# mimic4218_config.net
KiCad netlist of a schematic drawn in EAGLE
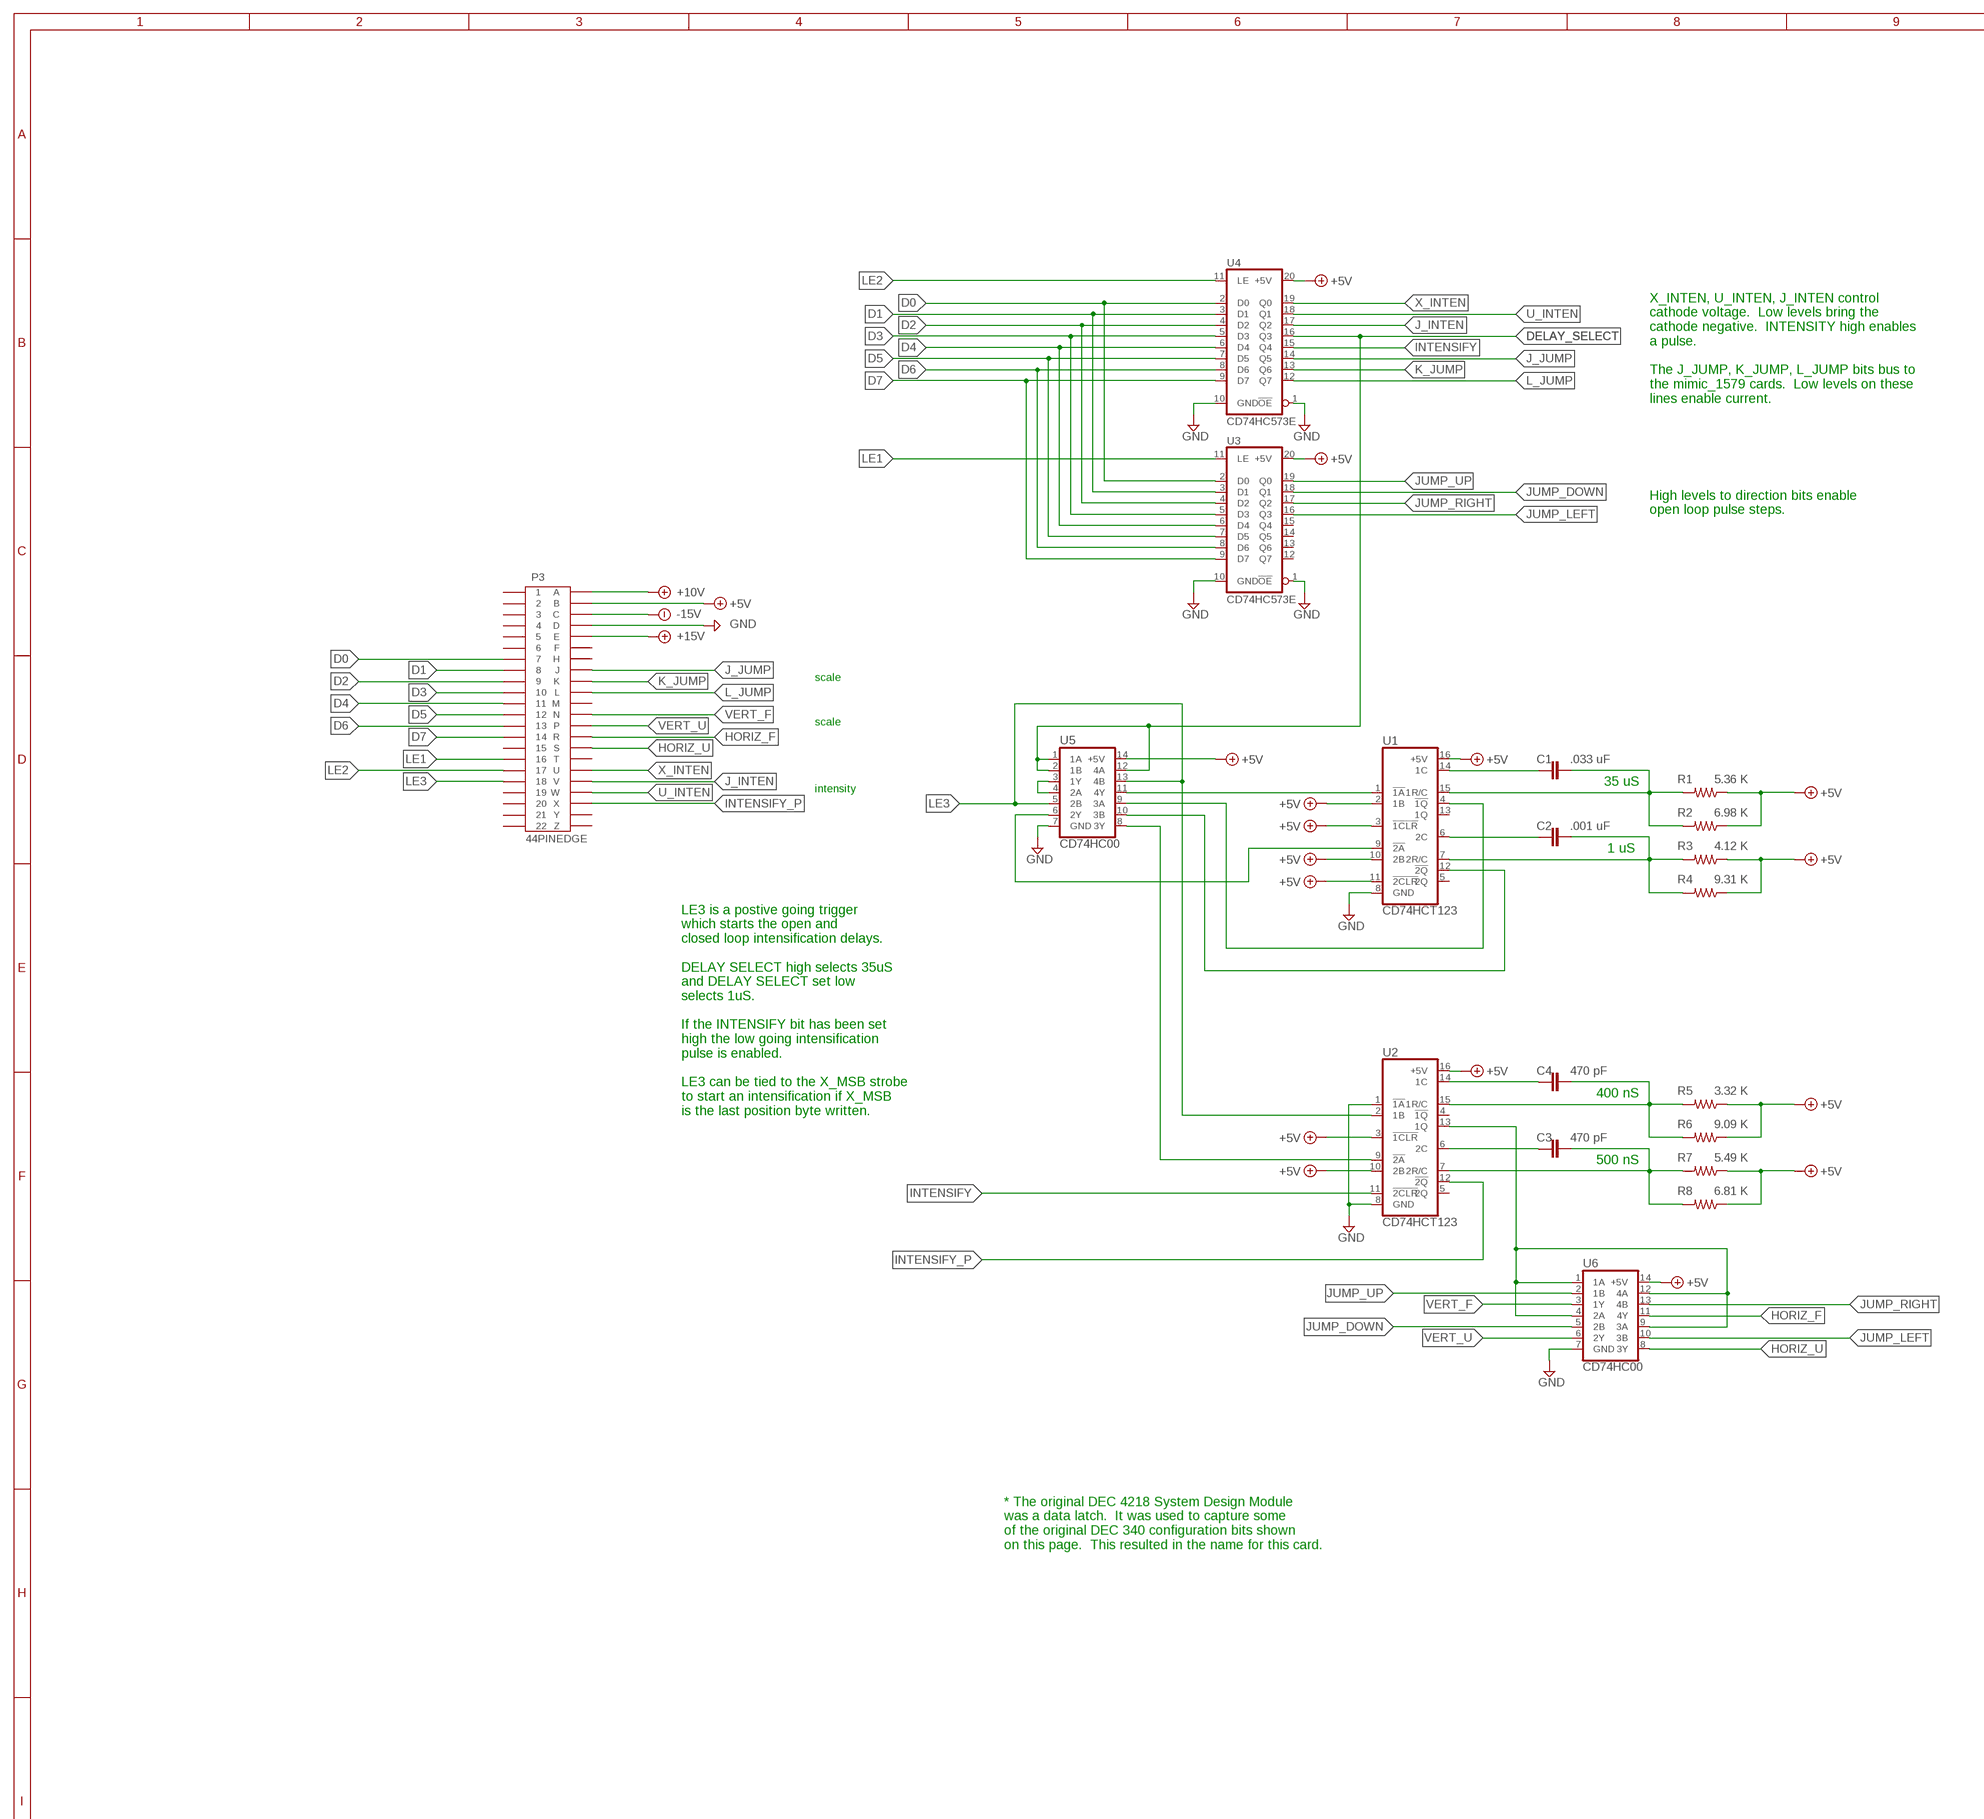
[diagram p0: schematic, sheet 1, part 1 of 2]
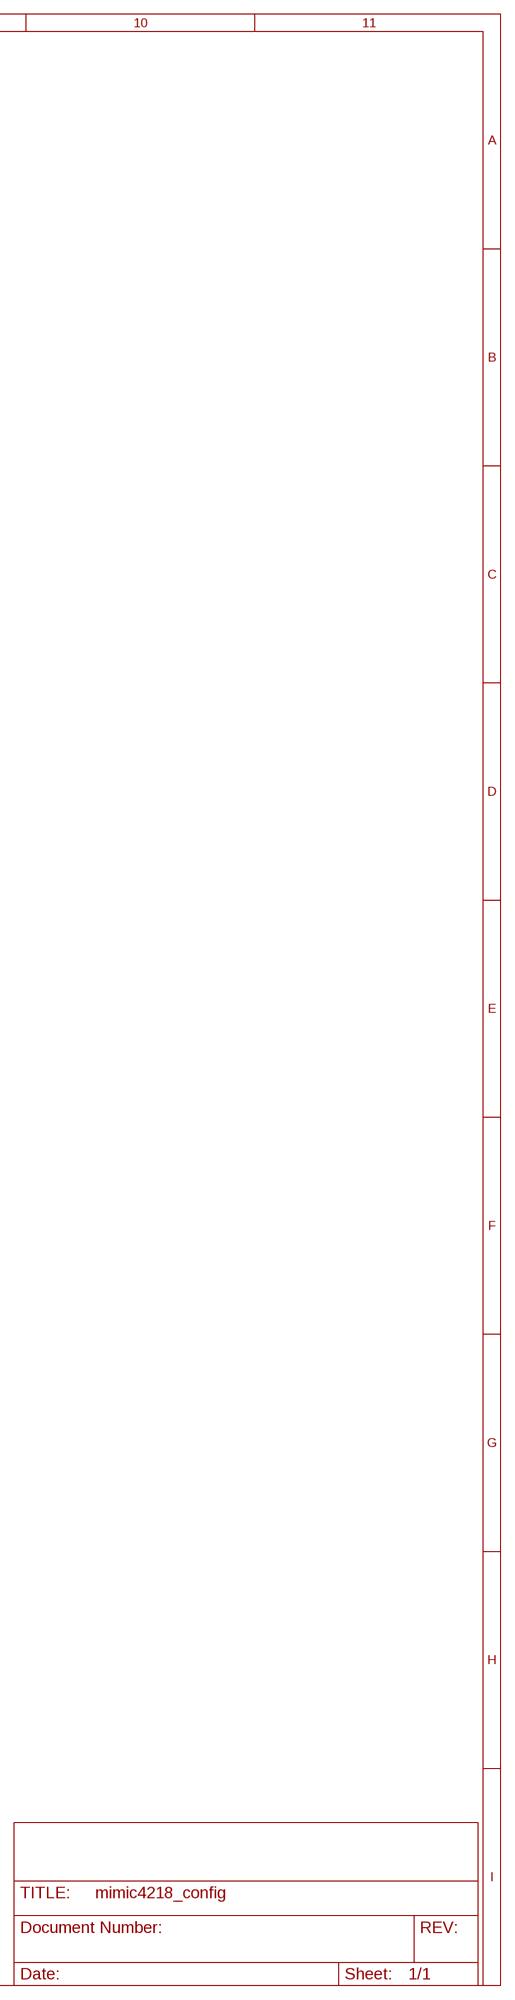
[diagram p1: schematic, sheet 1, part 2 of 2]

(export (version "E")
  (design (tool "Eeschema 10.0.6"))
  (components
    (comp (ref "C1")
      (value ".033 uF")
      (footprint "eagle-import:5MM_TH")
      (libsource (lib "eagle-import") (part "CAP_5MM"))
    )
    (comp (ref "C2")
      (value ".001 uF")
      (footprint "eagle-import:5MM_TH")
      (libsource (lib "eagle-import") (part "CAP_5MM"))
    )
    (comp (ref "C3")
      (value "470 pF")
      (footprint "eagle-import:5MM_TH")
      (libsource (lib "eagle-import") (part "CAP_5MM"))
    )
    (comp (ref "C4")
      (value "470 pF")
      (footprint "eagle-import:5MM_TH")
      (libsource (lib "eagle-import") (part "CAP_5MM"))
    )
    (comp (ref "P3")
      (value "44PINEDGE")
      (footprint "eagle-import:44PINEDGE")
      (libsource (lib "eagle-import") (part "44PINEDGE"))
    )
    (comp (ref "R1")
      (value "5.36 K")
      (footprint "eagle-import:0207_10")
      (libsource (lib "eagle-import") (part "R-1/4WATT"))
    )
    (comp (ref "R2")
      (value "6.98 K")
      (footprint "eagle-import:0207_10")
      (libsource (lib "eagle-import") (part "R-1/4WATT"))
    )
    (comp (ref "R3")
      (value "4.12 K")
      (footprint "eagle-import:0207_10")
      (libsource (lib "eagle-import") (part "R-1/4WATT"))
    )
    (comp (ref "R4")
      (value "9.31 K")
      (footprint "eagle-import:0207_10")
      (libsource (lib "eagle-import") (part "R-1/4WATT"))
    )
    (comp (ref "R5")
      (value "3.32 K")
      (footprint "eagle-import:0207_10")
      (libsource (lib "eagle-import") (part "R-1/4WATT"))
    )
    (comp (ref "R6")
      (value "9.09 K")
      (footprint "eagle-import:0207_10")
      (libsource (lib "eagle-import") (part "R-1/4WATT"))
    )
    (comp (ref "R7")
      (value "5.49 K")
      (footprint "eagle-import:0207_10")
      (libsource (lib "eagle-import") (part "R-1/4WATT"))
    )
    (comp (ref "R8")
      (value "6.81 K")
      (footprint "eagle-import:0207_10")
      (libsource (lib "eagle-import") (part "R-1/4WATT"))
    )
    (comp (ref "U1")
      (value "CD74HCT123")
      (footprint "eagle-import:DIP-16")
      (libsource (lib "eagle-import") (part "CD74HCT123"))
    )
    (comp (ref "U2")
      (value "CD74HCT123")
      (footprint "eagle-import:DIP-16")
      (libsource (lib "eagle-import") (part "CD74HCT123"))
    )
    (comp (ref "U3")
      (value "CD74HC573E")
      (footprint "eagle-import:DIP-20")
      (libsource (lib "eagle-import") (part "CD74HC573E"))
    )
    (comp (ref "U4")
      (value "CD74HC573E")
      (footprint "eagle-import:DIP-20")
      (libsource (lib "eagle-import") (part "CD74HC573E"))
    )
    (comp (ref "U5")
      (value "CD74HC00")
      (footprint "eagle-import:DIP-14")
      (libsource (lib "eagle-import") (part "CD74HC00"))
    )
    (comp (ref "U6")
      (value "CD74HC00")
      (footprint "eagle-import:DIP-14")
      (libsource (lib "eagle-import") (part "CD74HC00"))
    )
  )
  (nets
    (net (code "1") (name "+5V") (class "Default")
      (node (ref "P3") (pin "B") (pinfunction "B_B") (pintype "passive"))
      (node (ref "R1") (pin "1") (pinfunction "P$1_1") (pintype "passive"))
      (node (ref "R2") (pin "1") (pinfunction "P$1_1") (pintype "passive"))
      (node (ref "R3") (pin "1") (pinfunction "P$1_1") (pintype "passive"))
      (node (ref "R4") (pin "1") (pinfunction "P$1_1") (pintype "passive"))
      (node (ref "R5") (pin "1") (pinfunction "P$1_1") (pintype "passive"))
      (node (ref "R6") (pin "1") (pinfunction "P$1_1") (pintype "passive"))
      (node (ref "R7") (pin "1") (pinfunction "P$1_1") (pintype "passive"))
      (node (ref "R8") (pin "1") (pinfunction "P$1_1") (pintype "passive"))
      (node (ref "U1") (pin "10") (pinfunction "2B_10") (pintype "input"))
      (node (ref "U1") (pin "11") (pinfunction "~{2CLR}_11") (pintype "input"))
      (node (ref "U1") (pin "16") (pinfunction "+5V_16") (pintype "power_in"))
      (node (ref "U1") (pin "2") (pinfunction "1B_2") (pintype "input"))
      (node (ref "U1") (pin "3") (pinfunction "~{1CLR}_3") (pintype "input"))
      (node (ref "U2") (pin "10") (pinfunction "2B_10") (pintype "input"))
      (node (ref "U2") (pin "16") (pinfunction "+5V_16") (pintype "power_in"))
      (node (ref "U2") (pin "3") (pinfunction "~{1CLR}_3") (pintype "input"))
      (node (ref "U3") (pin "20") (pinfunction "+5V_20") (pintype "power_in"))
      (node (ref "U4") (pin "20") (pinfunction "+5V_20") (pintype "power_in"))
      (node (ref "U5") (pin "14") (pinfunction "+5V_14") (pintype "power_in"))
      (node (ref "U6") (pin "14") (pinfunction "+5V_14") (pintype "power_in"))
    )
    (net (code "2") (name "+10V") (class "Default")
      (node (ref "P3") (pin "A") (pinfunction "A_A") (pintype "passive"))
    )
    (net (code "3") (name "+15V") (class "Default")
      (node (ref "P3") (pin "E") (pinfunction "E_E") (pintype "passive"))
    )
    (net (code "4") (name "-15V") (class "Default")
      (node (ref "P3") (pin "C") (pinfunction "C_C") (pintype "passive"))
    )
    (net (code "5") (name "D0") (class "Default")
      (node (ref "P3") (pin "7") (pinfunction "7_7") (pintype "passive"))
      (node (ref "U3") (pin "2") (pinfunction "D0_2") (pintype "input"))
      (node (ref "U4") (pin "2") (pinfunction "D0_2") (pintype "input"))
    )
    (net (code "6") (name "D1") (class "Default")
      (node (ref "P3") (pin "8") (pinfunction "8_8") (pintype "passive"))
      (node (ref "U3") (pin "3") (pinfunction "D1_3") (pintype "input"))
      (node (ref "U4") (pin "3") (pinfunction "D1_3") (pintype "input"))
    )
    (net (code "7") (name "D2") (class "Default")
      (node (ref "P3") (pin "9") (pinfunction "9_9") (pintype "passive"))
      (node (ref "U3") (pin "4") (pinfunction "D2_4") (pintype "input"))
      (node (ref "U4") (pin "4") (pinfunction "D2_4") (pintype "input"))
    )
    (net (code "8") (name "D3") (class "Default")
      (node (ref "P3") (pin "10") (pinfunction "10_10") (pintype "passive"))
      (node (ref "U3") (pin "5") (pinfunction "D3_5") (pintype "input"))
      (node (ref "U4") (pin "5") (pinfunction "D3_5") (pintype "input"))
    )
    (net (code "9") (name "D4") (class "Default")
      (node (ref "P3") (pin "11") (pinfunction "11_11") (pintype "passive"))
      (node (ref "U3") (pin "6") (pinfunction "D4_6") (pintype "input"))
      (node (ref "U4") (pin "6") (pinfunction "D4_6") (pintype "input"))
    )
    (net (code "10") (name "D5") (class "Default")
      (node (ref "P3") (pin "12") (pinfunction "12_12") (pintype "passive"))
      (node (ref "U3") (pin "7") (pinfunction "D5_7") (pintype "input"))
      (node (ref "U4") (pin "7") (pinfunction "D5_7") (pintype "input"))
    )
    (net (code "11") (name "D6") (class "Default")
      (node (ref "P3") (pin "13") (pinfunction "13_13") (pintype "passive"))
      (node (ref "U3") (pin "8") (pinfunction "D6_8") (pintype "input"))
      (node (ref "U4") (pin "8") (pinfunction "D6_8") (pintype "input"))
    )
    (net (code "12") (name "D7") (class "Default")
      (node (ref "P3") (pin "14") (pinfunction "14_14") (pintype "passive"))
      (node (ref "U3") (pin "9") (pinfunction "D7_9") (pintype "input"))
      (node (ref "U4") (pin "9") (pinfunction "D7_9") (pintype "input"))
    )
    (net (code "13") (name "DELAY_SELECT") (class "Default")
      (node (ref "U4") (pin "16") (pinfunction "Q3_16") (pintype "tri_state"))
      (node (ref "U5") (pin "1") (pinfunction "1A_1") (pintype "input"))
      (node (ref "U5") (pin "12") (pinfunction "4A_12") (pintype "input"))
      (node (ref "U5") (pin "2") (pinfunction "1B_2") (pintype "input"))
    )
    (net (code "14") (name "GND") (class "Default")
      (node (ref "P3") (pin "D") (pinfunction "D_D") (pintype "passive"))
      (node (ref "U1") (pin "8") (pinfunction "GND_8") (pintype "power_in"))
      (node (ref "U2") (pin "1") (pinfunction "~{1A}_1") (pintype "input"))
      (node (ref "U2") (pin "8") (pinfunction "GND_8") (pintype "power_in"))
      (node (ref "U3") (pin "1") (pinfunction "~{OE}_1") (pintype "input"))
      (node (ref "U3") (pin "10") (pinfunction "GND_10") (pintype "power_in"))
      (node (ref "U4") (pin "1") (pinfunction "~{OE}_1") (pintype "input"))
      (node (ref "U4") (pin "10") (pinfunction "GND_10") (pintype "power_in"))
      (node (ref "U5") (pin "7") (pinfunction "GND_7") (pintype "power_in"))
      (node (ref "U6") (pin "7") (pinfunction "GND_7") (pintype "power_in"))
    )
    (net (code "15") (name "HORIZ_F") (class "Default")
      (node (ref "P3") (pin "R") (pinfunction "R_R") (pintype "passive"))
      (node (ref "U6") (pin "11") (pinfunction "4Y_11") (pintype "output"))
    )
    (net (code "16") (name "HORIZ_U") (class "Default")
      (node (ref "P3") (pin "S") (pinfunction "S_S") (pintype "passive"))
      (node (ref "U6") (pin "8") (pinfunction "3Y_8") (pintype "output"))
    )
    (net (code "17") (name "INTENSIFY") (class "Default")
      (node (ref "U2") (pin "11") (pinfunction "~{2CLR}_11") (pintype "input"))
      (node (ref "U4") (pin "15") (pinfunction "Q4_15") (pintype "tri_state"))
    )
    (net (code "18") (name "INTENSIFY_P") (class "Default")
      (node (ref "P3") (pin "X") (pinfunction "X_X") (pintype "passive"))
      (node (ref "U2") (pin "12") (pinfunction "~{2Q}_12") (pintype "output"))
    )
    (net (code "19") (name "JUMP_DOWN") (class "Default")
      (node (ref "U3") (pin "18") (pinfunction "Q1_18") (pintype "tri_state"))
      (node (ref "U6") (pin "5") (pinfunction "2B_5") (pintype "input"))
    )
    (net (code "20") (name "JUMP_LEFT") (class "Default")
      (node (ref "U3") (pin "16") (pinfunction "Q3_16") (pintype "tri_state"))
      (node (ref "U6") (pin "10") (pinfunction "3B_10") (pintype "input"))
    )
    (net (code "21") (name "JUMP_RIGHT") (class "Default")
      (node (ref "U3") (pin "17") (pinfunction "Q2_17") (pintype "tri_state"))
      (node (ref "U6") (pin "13") (pinfunction "4B_13") (pintype "input"))
    )
    (net (code "22") (name "JUMP_UP") (class "Default")
      (node (ref "U3") (pin "19") (pinfunction "Q0_19") (pintype "tri_state"))
      (node (ref "U6") (pin "2") (pinfunction "1B_2") (pintype "input"))
    )
    (net (code "23") (name "J_INTEN") (class "Default")
      (node (ref "P3") (pin "V") (pinfunction "V_V") (pintype "passive"))
      (node (ref "U4") (pin "17") (pinfunction "Q2_17") (pintype "tri_state"))
    )
    (net (code "24") (name "J_JUMP") (class "Default")
      (node (ref "P3") (pin "J") (pinfunction "J_J") (pintype "passive"))
      (node (ref "U4") (pin "14") (pinfunction "Q5_14") (pintype "tri_state"))
    )
    (net (code "25") (name "K_JUMP") (class "Default")
      (node (ref "P3") (pin "K") (pinfunction "K_K") (pintype "passive"))
      (node (ref "U4") (pin "13") (pinfunction "Q6_13") (pintype "tri_state"))
    )
    (net (code "26") (name "LE1") (class "Default")
      (node (ref "P3") (pin "16") (pinfunction "16_16") (pintype "passive"))
      (node (ref "U3") (pin "11") (pinfunction "LE_11") (pintype "input"))
    )
    (net (code "27") (name "LE2") (class "Default")
      (node (ref "P3") (pin "17") (pinfunction "17_17") (pintype "passive"))
      (node (ref "U4") (pin "11") (pinfunction "LE_11") (pintype "input"))
    )
    (net (code "28") (name "LE3") (class "Default")
      (node (ref "P3") (pin "18") (pinfunction "18_18") (pintype "passive"))
      (node (ref "U2") (pin "2") (pinfunction "1B_2") (pintype "input"))
      (node (ref "U5") (pin "13") (pinfunction "4B_13") (pintype "input"))
      (node (ref "U5") (pin "5") (pinfunction "2B_5") (pintype "input"))
    )
    (net (code "29") (name "L_JUMP") (class "Default")
      (node (ref "P3") (pin "L") (pinfunction "L_L") (pintype "passive"))
      (node (ref "U4") (pin "12") (pinfunction "Q7_12") (pintype "tri_state"))
    )
    (net (code "30") (name "Net-(R1-P$2)") (class "Default")
      (node (ref "C1") (pin "2") (pinfunction "2_2") (pintype "passive"))
      (node (ref "R1") (pin "2") (pinfunction "P$2_2") (pintype "passive"))
      (node (ref "R2") (pin "2") (pinfunction "P$2_2") (pintype "passive"))
      (node (ref "U1") (pin "15") (pinfunction "1R/C_15") (pintype "passive"))
    )
    (net (code "31") (name "Net-(R3-P$2)") (class "Default")
      (node (ref "C2") (pin "2") (pinfunction "2_2") (pintype "passive"))
      (node (ref "R3") (pin "2") (pinfunction "P$2_2") (pintype "passive"))
      (node (ref "R4") (pin "2") (pinfunction "P$2_2") (pintype "passive"))
      (node (ref "U1") (pin "7") (pinfunction "2R/C_7") (pintype "passive"))
    )
    (net (code "32") (name "Net-(R5-P$2)") (class "Default")
      (node (ref "C4") (pin "2") (pinfunction "2_2") (pintype "passive"))
      (node (ref "R5") (pin "2") (pinfunction "P$2_2") (pintype "passive"))
      (node (ref "R6") (pin "2") (pinfunction "P$2_2") (pintype "passive"))
      (node (ref "U2") (pin "15") (pinfunction "1R/C_15") (pintype "passive"))
    )
    (net (code "33") (name "Net-(R7-P$2)") (class "Default")
      (node (ref "C3") (pin "2") (pinfunction "2_2") (pintype "passive"))
      (node (ref "R7") (pin "2") (pinfunction "P$2_2") (pintype "passive"))
      (node (ref "R8") (pin "2") (pinfunction "P$2_2") (pintype "passive"))
      (node (ref "U2") (pin "7") (pinfunction "2R/C_7") (pintype "passive"))
    )
    (net (code "34") (name "Net-(U1-1C)") (class "Default")
      (node (ref "C1") (pin "1") (pinfunction "1_1") (pintype "passive"))
      (node (ref "U1") (pin "14") (pinfunction "1C_14") (pintype "passive"))
    )
    (net (code "35") (name "Net-(U1-2C)") (class "Default")
      (node (ref "C2") (pin "1") (pinfunction "1_1") (pintype "passive"))
      (node (ref "U1") (pin "6") (pinfunction "2C_6") (pintype "passive"))
    )
    (net (code "36") (name "Net-(U1-~{1A})") (class "Default")
      (node (ref "U1") (pin "1") (pinfunction "~{1A}_1") (pintype "input"))
      (node (ref "U5") (pin "11") (pinfunction "4Y_11") (pintype "output"))
    )
    (net (code "37") (name "Net-(U1-~{1Q})") (class "Default")
      (node (ref "U1") (pin "4") (pinfunction "~{1Q}_4") (pintype "output"))
      (node (ref "U5") (pin "9") (pinfunction "3A_9") (pintype "input"))
    )
    (net (code "38") (name "Net-(U1-~{2A})") (class "Default")
      (node (ref "U1") (pin "9") (pinfunction "~{2A}_9") (pintype "input"))
      (node (ref "U5") (pin "6") (pinfunction "2Y_6") (pintype "output"))
    )
    (net (code "39") (name "Net-(U1-~{2Q})") (class "Default")
      (node (ref "U1") (pin "12") (pinfunction "~{2Q}_12") (pintype "output"))
      (node (ref "U5") (pin "10") (pinfunction "3B_10") (pintype "input"))
    )
    (net (code "40") (name "Net-(U2-1C)") (class "Default")
      (node (ref "C4") (pin "1") (pinfunction "1_1") (pintype "passive"))
      (node (ref "U2") (pin "14") (pinfunction "1C_14") (pintype "passive"))
    )
    (net (code "41") (name "Net-(U2-1Q)") (class "Default")
      (node (ref "U2") (pin "13") (pinfunction "1Q_13") (pintype "output"))
      (node (ref "U6") (pin "1") (pinfunction "1A_1") (pintype "input"))
      (node (ref "U6") (pin "12") (pinfunction "4A_12") (pintype "input"))
      (node (ref "U6") (pin "4") (pinfunction "2A_4") (pintype "input"))
      (node (ref "U6") (pin "9") (pinfunction "3A_9") (pintype "input"))
    )
    (net (code "42") (name "Net-(U2-2C)") (class "Default")
      (node (ref "C3") (pin "1") (pinfunction "1_1") (pintype "passive"))
      (node (ref "U2") (pin "6") (pinfunction "2C_6") (pintype "passive"))
    )
    (net (code "43") (name "Net-(U2-~{2A})") (class "Default")
      (node (ref "U2") (pin "9") (pinfunction "~{2A}_9") (pintype "input"))
      (node (ref "U5") (pin "8") (pinfunction "3Y_8") (pintype "output"))
    )
    (net (code "44") (name "Net-(U5-1Y)") (class "Default")
      (node (ref "U5") (pin "3") (pinfunction "1Y_3") (pintype "output"))
      (node (ref "U5") (pin "4") (pinfunction "2A_4") (pintype "input"))
    )
    (net (code "45") (name "U_INTEN") (class "Default")
      (node (ref "P3") (pin "W") (pinfunction "W_W") (pintype "passive"))
      (node (ref "U4") (pin "18") (pinfunction "Q1_18") (pintype "tri_state"))
    )
    (net (code "46") (name "VERT_F") (class "Default")
      (node (ref "P3") (pin "N") (pinfunction "N_N") (pintype "passive"))
      (node (ref "U6") (pin "3") (pinfunction "1Y_3") (pintype "output"))
    )
    (net (code "47") (name "VERT_U") (class "Default")
      (node (ref "P3") (pin "P") (pinfunction "P_P") (pintype "passive"))
      (node (ref "U6") (pin "6") (pinfunction "2Y_6") (pintype "output"))
    )
    (net (code "48") (name "X_INTEN") (class "Default")
      (node (ref "P3") (pin "U") (pinfunction "U_U") (pintype "passive"))
      (node (ref "U4") (pin "19") (pinfunction "Q0_19") (pintype "tri_state"))
    )
    (net (code "49") (name "unconnected-(P3-Pad1)") (class "Default")
      (node (ref "P3") (pin "1") (pinfunction "1_1") (pintype "passive"))
    )
    (net (code "50") (name "unconnected-(P3-Pad2)") (class "Default")
      (node (ref "P3") (pin "2") (pinfunction "2_2") (pintype "passive"))
    )
    (net (code "51") (name "unconnected-(P3-Pad3)") (class "Default")
      (node (ref "P3") (pin "3") (pinfunction "3_3") (pintype "passive"))
    )
    (net (code "52") (name "unconnected-(P3-Pad4)") (class "Default")
      (node (ref "P3") (pin "4") (pinfunction "4_4") (pintype "passive"))
    )
    (net (code "53") (name "unconnected-(P3-Pad5)") (class "Default")
      (node (ref "P3") (pin "5") (pinfunction "5_5") (pintype "passive"))
    )
    (net (code "54") (name "unconnected-(P3-Pad6)") (class "Default")
      (node (ref "P3") (pin "6") (pinfunction "6_6") (pintype "passive"))
    )
    (net (code "55") (name "unconnected-(P3-Pad15)") (class "Default")
      (node (ref "P3") (pin "15") (pinfunction "15_15") (pintype "passive"))
    )
    (net (code "56") (name "unconnected-(P3-Pad19)") (class "Default")
      (node (ref "P3") (pin "19") (pinfunction "19_19") (pintype "passive"))
    )
    (net (code "57") (name "unconnected-(P3-Pad20)") (class "Default")
      (node (ref "P3") (pin "20") (pinfunction "20_20") (pintype "passive"))
    )
    (net (code "58") (name "unconnected-(P3-Pad21)") (class "Default")
      (node (ref "P3") (pin "21") (pinfunction "21_21") (pintype "passive"))
    )
    (net (code "59") (name "unconnected-(P3-Pad22)") (class "Default")
      (node (ref "P3") (pin "22") (pinfunction "22_22") (pintype "passive"))
    )
    (net (code "60") (name "unconnected-(P3-PadF)") (class "Default")
      (node (ref "P3") (pin "F") (pinfunction "F_F") (pintype "passive"))
    )
    (net (code "61") (name "unconnected-(P3-PadH)") (class "Default")
      (node (ref "P3") (pin "H") (pinfunction "H_H") (pintype "passive"))
    )
    (net (code "62") (name "unconnected-(P3-PadM)") (class "Default")
      (node (ref "P3") (pin "M") (pinfunction "M_M") (pintype "passive"))
    )
    (net (code "63") (name "unconnected-(P3-PadT)") (class "Default")
      (node (ref "P3") (pin "T") (pinfunction "T_T") (pintype "passive"))
    )
    (net (code "64") (name "unconnected-(P3-PadY)") (class "Default")
      (node (ref "P3") (pin "Y") (pinfunction "Y_Y") (pintype "passive"))
    )
    (net (code "65") (name "unconnected-(P3-PadZ)") (class "Default")
      (node (ref "P3") (pin "Z") (pinfunction "Z_Z") (pintype "passive"))
    )
    (net (code "66") (name "unconnected-(U1-1Q-Pad13)") (class "Default")
      (node (ref "U1") (pin "13") (pinfunction "1Q_13") (pintype "output"))
    )
    (net (code "67") (name "unconnected-(U1-2Q-Pad5)") (class "Default")
      (node (ref "U1") (pin "5") (pinfunction "2Q_5") (pintype "output"))
    )
    (net (code "68") (name "unconnected-(U2-2Q-Pad5)") (class "Default")
      (node (ref "U2") (pin "5") (pinfunction "2Q_5") (pintype "output"))
    )
    (net (code "69") (name "unconnected-(U2-~{1Q}-Pad4)") (class "Default")
      (node (ref "U2") (pin "4") (pinfunction "~{1Q}_4") (pintype "output"))
    )
    (net (code "70") (name "unconnected-(U3-Q4-Pad15)") (class "Default")
      (node (ref "U3") (pin "15") (pinfunction "Q4_15") (pintype "tri_state"))
    )
    (net (code "71") (name "unconnected-(U3-Q5-Pad14)") (class "Default")
      (node (ref "U3") (pin "14") (pinfunction "Q5_14") (pintype "tri_state"))
    )
    (net (code "72") (name "unconnected-(U3-Q6-Pad13)") (class "Default")
      (node (ref "U3") (pin "13") (pinfunction "Q6_13") (pintype "tri_state"))
    )
    (net (code "73") (name "unconnected-(U3-Q7-Pad12)") (class "Default")
      (node (ref "U3") (pin "12") (pinfunction "Q7_12") (pintype "tri_state"))
    )
  )
)
